# Western_Aero_2020.net
KiCad netlist of a schematic drawn in EAGLE
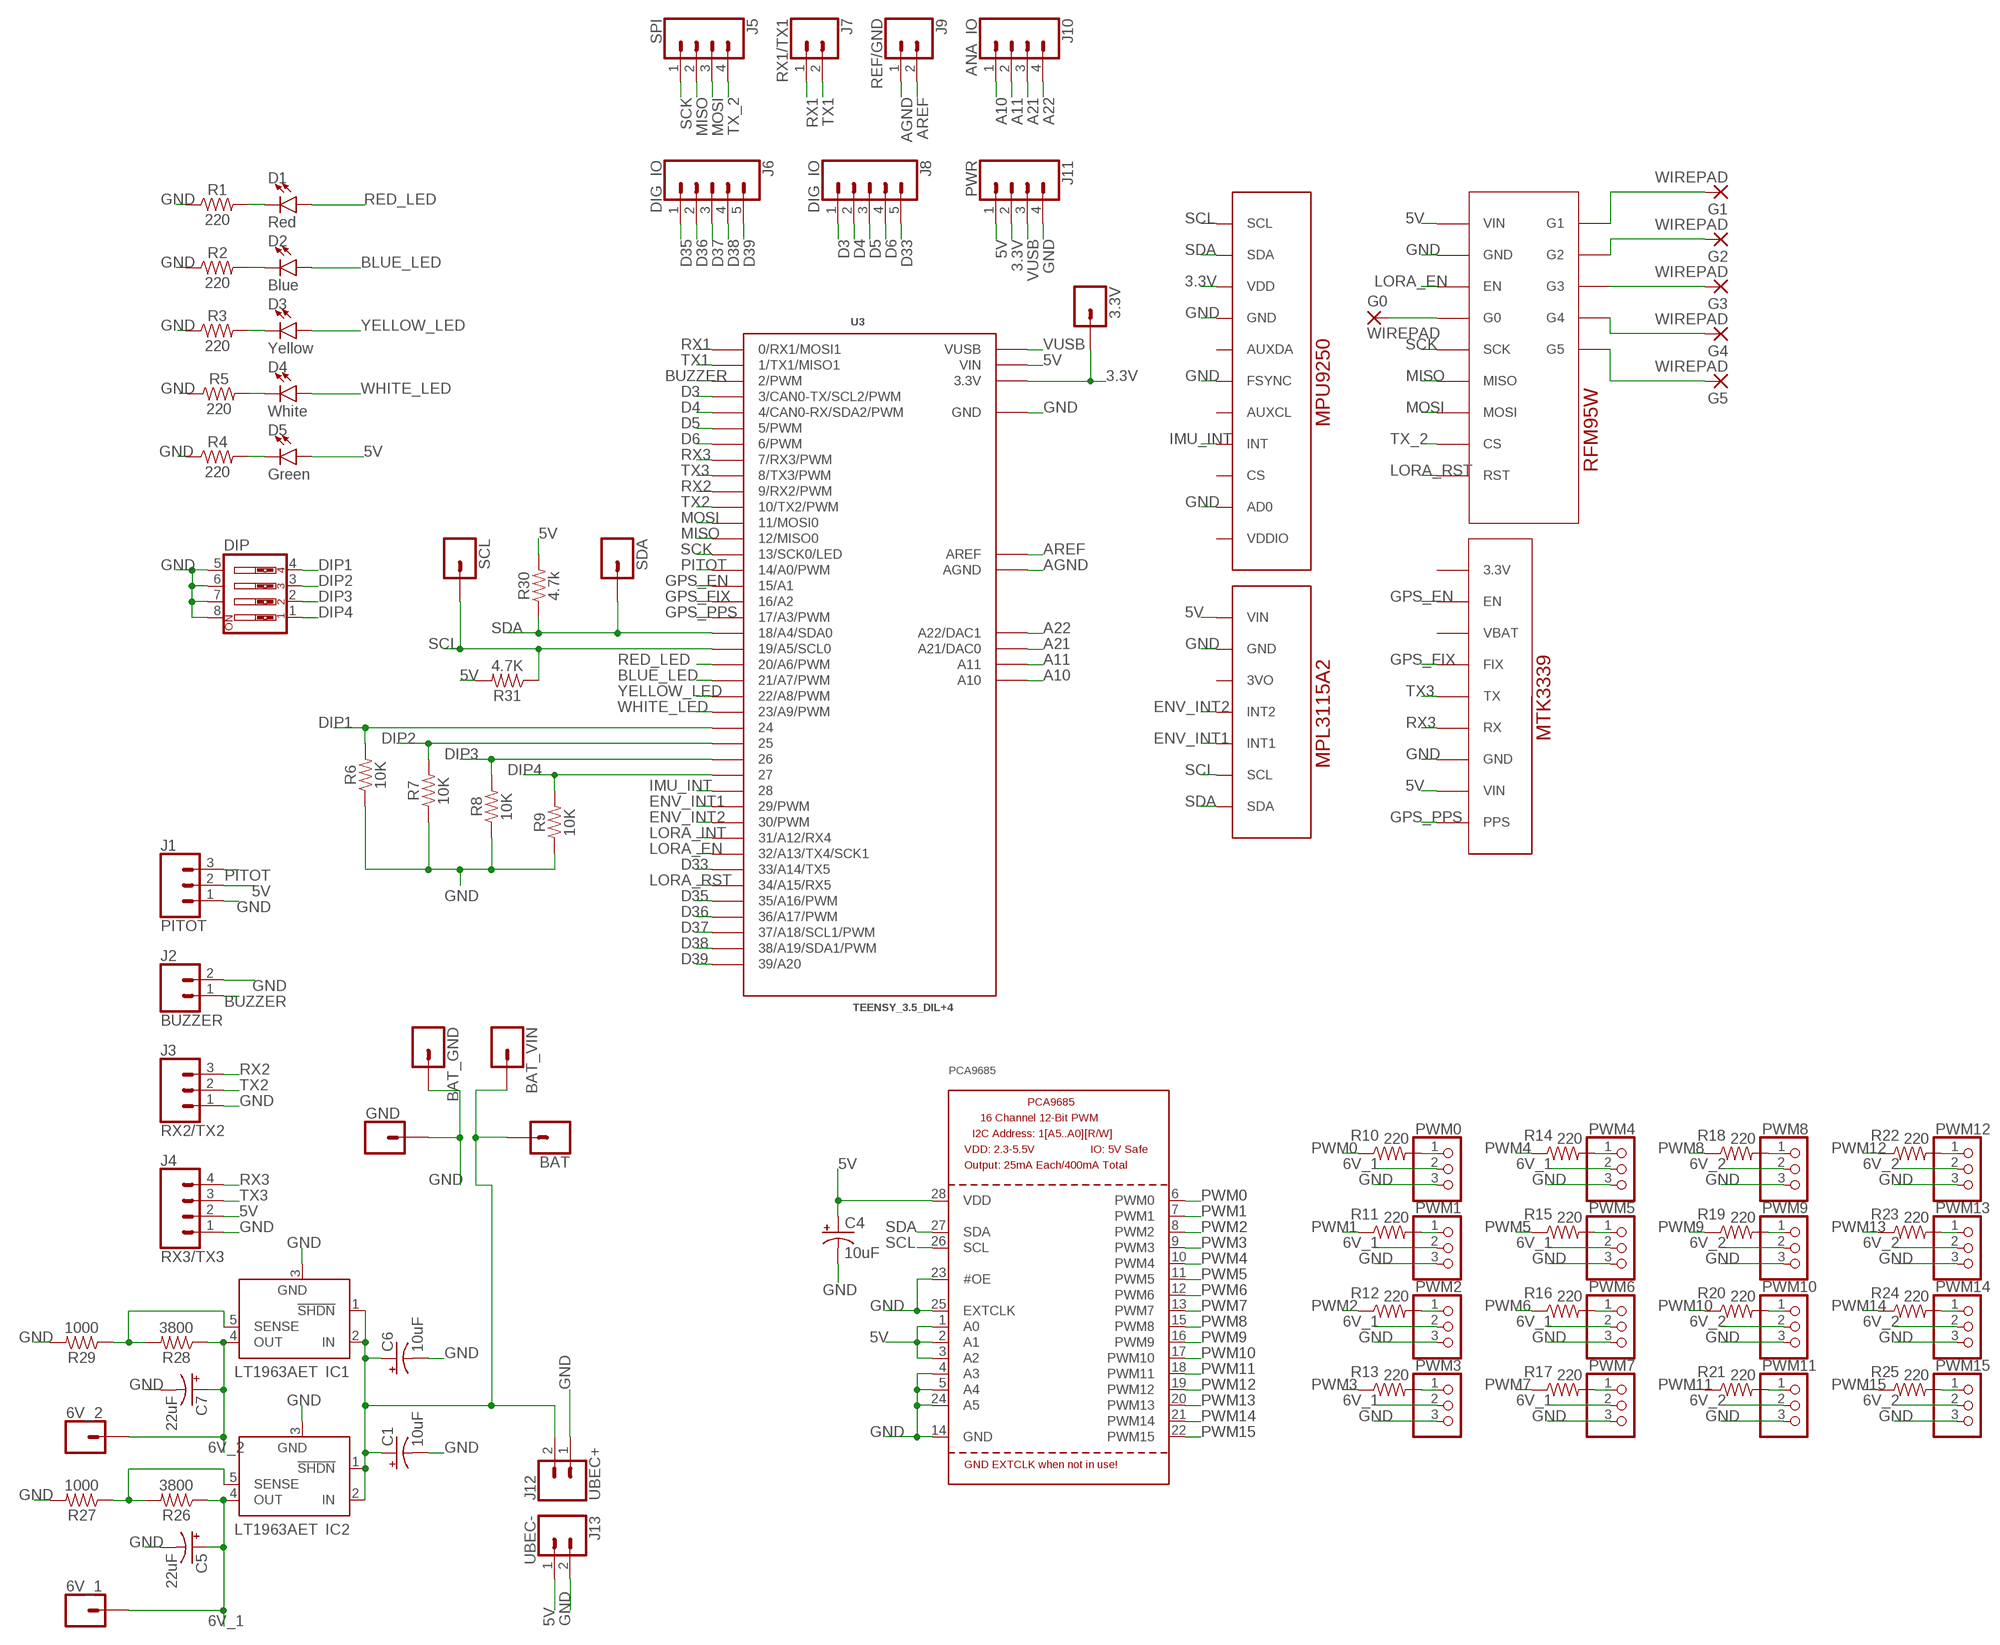
[diagram p0: schematic, sheet 1]

(export (version "E")
  (design (tool "Eeschema 10.0.6"))
  (components
    (comp (ref "3.3V")
      (value "CONN_01")
      (footprint "eagle-import:1X01")
      (libsource (lib "eagle-import") (part "CONN_01"))
    )
    (comp (ref "6V_1")
      (value "CONN_01")
      (footprint "eagle-import:1X01")
      (libsource (lib "eagle-import") (part "CONN_01"))
    )
    (comp (ref "6V_2")
      (value "CONN_01")
      (footprint "eagle-import:1X01")
      (libsource (lib "eagle-import") (part "CONN_01"))
    )
    (comp (ref "BAT")
      (value "CONN_01")
      (footprint "eagle-import:1X01")
      (libsource (lib "eagle-import") (part "CONN_01"))
    )
    (comp (ref "BAT_GND")
      (value "CONN_01")
      (footprint "eagle-import:1X01")
      (libsource (lib "eagle-import") (part "CONN_01"))
    )
    (comp (ref "BAT_VIN")
      (value "CONN_01")
      (footprint "eagle-import:1X01")
      (libsource (lib "eagle-import") (part "CONN_01"))
    )
    (comp (ref "C1")
      (value "10uF")
      (footprint "eagle-import:CPOL-RADIAL-2.5MM-5MM")
      (libsource (lib "eagle-import") (part "10UF-POLAR-RADIAL-2.5MM-25V-20%"))
    )
    (comp (ref "C4")
      (value "10uF")
      (footprint "eagle-import:CPOL-RADIAL-2.5MM-5MM")
      (libsource (lib "eagle-import") (part "10UF-POLAR-RADIAL-2.5MM-25V-20%"))
    )
    (comp (ref "C5")
      (value "22uF")
      (footprint "eagle-import:CPOL-RADIAL-2.5MM-5MM")
      (libsource (lib "eagle-import") (part "10UF-POLAR-RADIAL-2.5MM-25V-20%"))
    )
    (comp (ref "C6")
      (value "10uF")
      (footprint "eagle-import:CPOL-RADIAL-2.5MM-5MM")
      (libsource (lib "eagle-import") (part "10UF-POLAR-RADIAL-2.5MM-25V-20%"))
    )
    (comp (ref "C7")
      (value "22uF")
      (footprint "eagle-import:CPOL-RADIAL-2.5MM-5MM")
      (libsource (lib "eagle-import") (part "10UF-POLAR-RADIAL-2.5MM-25V-20%"))
    )
    (comp (ref "D1")
      (value "Red")
      (footprint "eagle-import:LED_3MM")
      (libsource (lib "eagle-import") (part "LED3MM"))
    )
    (comp (ref "D2")
      (value "Blue")
      (footprint "eagle-import:LED_3MM")
      (libsource (lib "eagle-import") (part "LED3MM"))
    )
    (comp (ref "D3")
      (value "Yellow")
      (footprint "eagle-import:LED_3MM")
      (libsource (lib "eagle-import") (part "LED3MM"))
    )
    (comp (ref "D4")
      (value "White")
      (footprint "eagle-import:LED_3MM")
      (libsource (lib "eagle-import") (part "LED3MM"))
    )
    (comp (ref "D5")
      (value "Green")
      (footprint "eagle-import:LED_3MM")
      (libsource (lib "eagle-import") (part "LED3MM"))
    )
    (comp (ref "DIP")
      (value "SW_DIP-4")
      (footprint "eagle-import:EDG-04")
      (libsource (lib "eagle-import") (part "SW_DIP-4"))
    )
    (comp (ref "G0")
      (value "WIREPAD")
      (footprint "eagle-import:2,15_1,0")
      (libsource (lib "eagle-import") (part "WIREPAD2,15/1,0"))
    )
    (comp (ref "G1")
      (value "WIREPAD")
      (footprint "eagle-import:2,15_1,0")
      (libsource (lib "eagle-import") (part "WIREPAD2,15/1,0"))
    )
    (comp (ref "G2")
      (value "WIREPAD")
      (footprint "eagle-import:2,15_1,0")
      (libsource (lib "eagle-import") (part "WIREPAD2,15/1,0"))
    )
    (comp (ref "G3")
      (value "WIREPAD")
      (footprint "eagle-import:2,15_1,0")
      (libsource (lib "eagle-import") (part "WIREPAD2,15/1,0"))
    )
    (comp (ref "G4")
      (value "WIREPAD")
      (footprint "eagle-import:2,15_1,0")
      (libsource (lib "eagle-import") (part "WIREPAD2,15/1,0"))
    )
    (comp (ref "G5")
      (value "WIREPAD")
      (footprint "eagle-import:2,15_1,0")
      (libsource (lib "eagle-import") (part "WIREPAD2,15/1,0"))
    )
    (comp (ref "GND")
      (value "CONN_01")
      (footprint "eagle-import:1X01")
      (libsource (lib "eagle-import") (part "CONN_01"))
    )
    (comp (ref "IC1")
      (value "LT1963AET")
      (footprint "eagle-import:TO220-5")
      (libsource (lib "eagle-import") (part "LT1963AET"))
    )
    (comp (ref "IC2")
      (value "LT1963AET")
      (footprint "eagle-import:TO220-5")
      (libsource (lib "eagle-import") (part "LT1963AET"))
    )
    (comp (ref "J1")
      (value "PITOT")
      (footprint "eagle-import:1X03")
      (libsource (lib "eagle-import") (part "CONN_03"))
    )
    (comp (ref "J2")
      (value "BUZZER")
      (footprint "eagle-import:1X02")
      (libsource (lib "eagle-import") (part "CONN_02"))
    )
    (comp (ref "J3")
      (value "RX2/TX2")
      (footprint "eagle-import:1X03")
      (libsource (lib "eagle-import") (part "CONN_03"))
    )
    (comp (ref "J4")
      (value "RX3/TX3")
      (footprint "eagle-import:1X04")
      (libsource (lib "eagle-import") (part "CONN_04"))
    )
    (comp (ref "J5")
      (value "SPI")
      (footprint "eagle-import:1X04")
      (libsource (lib "eagle-import") (part "CONN_04"))
    )
    (comp (ref "J6")
      (value "DIG_IO")
      (footprint "eagle-import:1X05")
      (libsource (lib "eagle-import") (part "CONN_05"))
    )
    (comp (ref "J7")
      (value "RX1/TX1")
      (footprint "eagle-import:1X02")
      (libsource (lib "eagle-import") (part "CONN_02"))
    )
    (comp (ref "J8")
      (value "DIG_IO")
      (footprint "eagle-import:1X05")
      (libsource (lib "eagle-import") (part "CONN_05"))
    )
    (comp (ref "J9")
      (value "REF/GND")
      (footprint "eagle-import:1X02")
      (libsource (lib "eagle-import") (part "CONN_02"))
    )
    (comp (ref "J10")
      (value "ANA_IO")
      (footprint "eagle-import:1X04")
      (libsource (lib "eagle-import") (part "CONN_04"))
    )
    (comp (ref "J11")
      (value "PWR")
      (footprint "eagle-import:1X04")
      (libsource (lib "eagle-import") (part "CONN_04"))
    )
    (comp (ref "J12")
      (value "UBEC+")
      (footprint "eagle-import:1X02")
      (libsource (lib "eagle-import") (part "CONN_02"))
    )
    (comp (ref "J13")
      (value "UBEC-")
      (footprint "eagle-import:1X02")
      (libsource (lib "eagle-import") (part "CONN_02"))
    )
    (comp (ref "JP1")
      (value "PWM0")
      (footprint "eagle-import:1X03")
      (libsource (lib "eagle-import") (part "PINHD-1X3"))
    )
    (comp (ref "JP2")
      (value "PWM1")
      (footprint "eagle-import:1X03")
      (libsource (lib "eagle-import") (part "PINHD-1X3"))
    )
    (comp (ref "JP3")
      (value "PWM2")
      (footprint "eagle-import:1X03")
      (libsource (lib "eagle-import") (part "PINHD-1X3"))
    )
    (comp (ref "JP4")
      (value "PWM3")
      (footprint "eagle-import:1X03")
      (libsource (lib "eagle-import") (part "PINHD-1X3"))
    )
    (comp (ref "JP5")
      (value "PWM4")
      (footprint "eagle-import:1X03")
      (libsource (lib "eagle-import") (part "PINHD-1X3"))
    )
    (comp (ref "JP6")
      (value "PWM5")
      (footprint "eagle-import:1X03")
      (libsource (lib "eagle-import") (part "PINHD-1X3"))
    )
    (comp (ref "JP7")
      (value "PWM6")
      (footprint "eagle-import:1X03")
      (libsource (lib "eagle-import") (part "PINHD-1X3"))
    )
    (comp (ref "JP8")
      (value "PWM7")
      (footprint "eagle-import:1X03")
      (libsource (lib "eagle-import") (part "PINHD-1X3"))
    )
    (comp (ref "JP9")
      (value "PWM8")
      (footprint "eagle-import:1X03")
      (libsource (lib "eagle-import") (part "PINHD-1X3"))
    )
    (comp (ref "JP10")
      (value "PWM9")
      (footprint "eagle-import:1X03")
      (libsource (lib "eagle-import") (part "PINHD-1X3"))
    )
    (comp (ref "JP11")
      (value "PWM10")
      (footprint "eagle-import:1X03")
      (libsource (lib "eagle-import") (part "PINHD-1X3"))
    )
    (comp (ref "JP12")
      (value "PWM11")
      (footprint "eagle-import:1X03")
      (libsource (lib "eagle-import") (part "PINHD-1X3"))
    )
    (comp (ref "JP13")
      (value "PWM12")
      (footprint "eagle-import:1X03")
      (libsource (lib "eagle-import") (part "PINHD-1X3"))
    )
    (comp (ref "JP14")
      (value "PWM13")
      (footprint "eagle-import:1X03")
      (libsource (lib "eagle-import") (part "PINHD-1X3"))
    )
    (comp (ref "JP15")
      (value "PWM14")
      (footprint "eagle-import:1X03")
      (libsource (lib "eagle-import") (part "PINHD-1X3"))
    )
    (comp (ref "JP16")
      (value "PWM15")
      (footprint "eagle-import:1X03")
      (libsource (lib "eagle-import") (part "PINHD-1X3"))
    )
    (comp (ref "PCA9685")
      (value "PCA9685")
      (footprint "eagle-import:TSSOP28")
      (libsource (lib "eagle-import") (part "PCA9685"))
    )
    (comp (ref "R1")
      (value "220")
      (footprint "eagle-import:AXIAL-0.3")
      (libsource (lib "eagle-import") (part "330OHM-HORIZ-1/10W-5%"))
    )
    (comp (ref "R2")
      (value "220")
      (footprint "eagle-import:AXIAL-0.3")
      (libsource (lib "eagle-import") (part "330OHM-HORIZ-1/10W-5%"))
    )
    (comp (ref "R3")
      (value "220")
      (footprint "eagle-import:AXIAL-0.3")
      (libsource (lib "eagle-import") (part "330OHM-HORIZ-1/10W-5%"))
    )
    (comp (ref "R4")
      (value "220")
      (footprint "eagle-import:AXIAL-0.3")
      (libsource (lib "eagle-import") (part "330OHM-HORIZ-1/10W-5%"))
    )
    (comp (ref "R5")
      (value "220")
      (footprint "eagle-import:AXIAL-0.3")
      (libsource (lib "eagle-import") (part "330OHM-HORIZ-1/10W-5%"))
    )
    (comp (ref "R6")
      (value "10K")
      (footprint "eagle-import:AXIAL-0.3")
      (libsource (lib "eagle-import") (part "330OHM-HORIZ-1/10W-5%"))
    )
    (comp (ref "R7")
      (value "10K")
      (footprint "eagle-import:AXIAL-0.3")
      (libsource (lib "eagle-import") (part "330OHM-HORIZ-1/10W-5%"))
    )
    (comp (ref "R8")
      (value "10K")
      (footprint "eagle-import:AXIAL-0.3")
      (libsource (lib "eagle-import") (part "330OHM-HORIZ-1/10W-5%"))
    )
    (comp (ref "R9")
      (value "10K")
      (footprint "eagle-import:AXIAL-0.3")
      (libsource (lib "eagle-import") (part "330OHM-HORIZ-1/10W-5%"))
    )
    (comp (ref "R10")
      (value "220")
      (footprint "eagle-import:AXIAL-0.3")
      (libsource (lib "eagle-import") (part "330OHM-HORIZ-1/10W-5%"))
    )
    (comp (ref "R11")
      (value "220")
      (footprint "eagle-import:AXIAL-0.3")
      (libsource (lib "eagle-import") (part "330OHM-HORIZ-1/10W-5%"))
    )
    (comp (ref "R12")
      (value "220")
      (footprint "eagle-import:AXIAL-0.3")
      (libsource (lib "eagle-import") (part "330OHM-HORIZ-1/10W-5%"))
    )
    (comp (ref "R13")
      (value "220")
      (footprint "eagle-import:AXIAL-0.3")
      (libsource (lib "eagle-import") (part "330OHM-HORIZ-1/10W-5%"))
    )
    (comp (ref "R14")
      (value "220")
      (footprint "eagle-import:AXIAL-0.3")
      (libsource (lib "eagle-import") (part "330OHM-HORIZ-1/10W-5%"))
    )
    (comp (ref "R15")
      (value "220")
      (footprint "eagle-import:AXIAL-0.3")
      (libsource (lib "eagle-import") (part "330OHM-HORIZ-1/10W-5%"))
    )
    (comp (ref "R16")
      (value "220")
      (footprint "eagle-import:AXIAL-0.3")
      (libsource (lib "eagle-import") (part "330OHM-HORIZ-1/10W-5%"))
    )
    (comp (ref "R17")
      (value "220")
      (footprint "eagle-import:AXIAL-0.3")
      (libsource (lib "eagle-import") (part "330OHM-HORIZ-1/10W-5%"))
    )
    (comp (ref "R18")
      (value "220")
      (footprint "eagle-import:AXIAL-0.3")
      (libsource (lib "eagle-import") (part "330OHM-HORIZ-1/10W-5%"))
    )
    (comp (ref "R19")
      (value "220")
      (footprint "eagle-import:AXIAL-0.3")
      (libsource (lib "eagle-import") (part "330OHM-HORIZ-1/10W-5%"))
    )
    (comp (ref "R20")
      (value "220")
      (footprint "eagle-import:AXIAL-0.3")
      (libsource (lib "eagle-import") (part "330OHM-HORIZ-1/10W-5%"))
    )
    (comp (ref "R21")
      (value "220")
      (footprint "eagle-import:AXIAL-0.3")
      (libsource (lib "eagle-import") (part "330OHM-HORIZ-1/10W-5%"))
    )
    (comp (ref "R22")
      (value "220")
      (footprint "eagle-import:AXIAL-0.3")
      (libsource (lib "eagle-import") (part "330OHM-HORIZ-1/10W-5%"))
    )
    (comp (ref "R23")
      (value "220")
      (footprint "eagle-import:AXIAL-0.3")
      (libsource (lib "eagle-import") (part "330OHM-HORIZ-1/10W-5%"))
    )
    (comp (ref "R24")
      (value "220")
      (footprint "eagle-import:AXIAL-0.3")
      (libsource (lib "eagle-import") (part "330OHM-HORIZ-1/10W-5%"))
    )
    (comp (ref "R25")
      (value "220")
      (footprint "eagle-import:AXIAL-0.3")
      (libsource (lib "eagle-import") (part "330OHM-HORIZ-1/10W-5%"))
    )
    (comp (ref "R26")
      (value "3800")
      (footprint "eagle-import:AXIAL-0.3")
      (libsource (lib "eagle-import") (part "330OHM-HORIZ-1/10W-5%"))
    )
    (comp (ref "R27")
      (value "1000")
      (footprint "eagle-import:AXIAL-0.3")
      (libsource (lib "eagle-import") (part "330OHM-HORIZ-1/10W-5%"))
    )
    (comp (ref "R28")
      (value "3800")
      (footprint "eagle-import:AXIAL-0.3")
      (libsource (lib "eagle-import") (part "330OHM-HORIZ-1/10W-5%"))
    )
    (comp (ref "R29")
      (value "1000")
      (footprint "eagle-import:AXIAL-0.3")
      (libsource (lib "eagle-import") (part "330OHM-HORIZ-1/10W-5%"))
    )
    (comp (ref "R30")
      (value "4.7k")
      (footprint "eagle-import:AXIAL-0.3")
      (libsource (lib "eagle-import") (part "330OHM-HORIZ-1/10W-5%"))
    )
    (comp (ref "R31")
      (value "4.7K")
      (footprint "eagle-import:AXIAL-0.3")
      (libsource (lib "eagle-import") (part "330OHM-HORIZ-1/10W-5%"))
    )
    (comp (ref "SCL")
      (value "CONN_01")
      (footprint "eagle-import:1X01")
      (libsource (lib "eagle-import") (part "CONN_01"))
    )
    (comp (ref "SDA")
      (value "CONN_01")
      (footprint "eagle-import:1X01")
      (libsource (lib "eagle-import") (part "CONN_01"))
    )
    (comp (ref "U3")
      (value "TEENSY_3.5_DIL+4")
      (footprint "eagle-import:TEENSY_3.5_DIL+4")
      (libsource (lib "eagle-import") (part "TEENSY_3.5_DIL+4"))
    )
    (comp (ref "U5")
      (value "SPARKFUN_MPU9250_IMU")
      (footprint "eagle-import:SPARKFUN_MPU9250_IMU")
      (libsource (lib "eagle-import") (part "SPARKFUN_MPU9250_IMU"))
    )
    (comp (ref "U6")
      (value "ADAFRUIT_MPL3115A2_BAROMETER")
      (footprint "eagle-import:ADAFRUIT_MPL3115A2_BAROMETER")
      (libsource (lib "eagle-import") (part "ADAFRUIT_MPL3115A2_BAROMETER"))
    )
    (comp (ref "U8")
      (value "ADAFRUIT_RFM95W_LORA_RADIO")
      (footprint "eagle-import:ADAFRUIT_RFM95W_LORA_RADIO")
      (libsource (lib "eagle-import") (part "ADAFRUIT_RFM95W_LORA_RADIO"))
    )
    (comp (ref "U9")
      (value "ADAFRUIT_MTK3339_GPS")
      (footprint "eagle-import:ADAFRUIT_MTK3339_GPS")
      (libsource (lib "eagle-import") (part "ADAFRUIT_MTK3339_GPS"))
    )
  )
  (nets
    (net (code "1") (name "/3.3V") (class "Default")
      (node (ref "3.3V") (pin "1") (pinfunction "1_1") (pintype "passive"))
      (node (ref "J11") (pin "2") (pinfunction "2_2") (pintype "passive"))
      (node (ref "U3") (pin "3.3V") (pinfunction "3.3V_3.3V") (pintype "power_in"))
      (node (ref "U3") (pin "3.3V3") (pinfunction "3.3V_3.3V3") (pintype "power_in"))
      (node (ref "U5") (pin "VDD") (pinfunction "VDD_VDD") (pintype "bidirectional"))
    )
    (net (code "2") (name "/5V") (class "Default")
      (node (ref "C4") (pin "1") (pinfunction "+_1") (pintype "passive"))
      (node (ref "D5") (pin "A") (pinfunction "A_A") (pintype "passive"))
      (node (ref "J1") (pin "2") (pinfunction "2_2") (pintype "passive"))
      (node (ref "J11") (pin "1") (pinfunction "1_1") (pintype "passive"))
      (node (ref "J13") (pin "1") (pinfunction "1_1") (pintype "passive"))
      (node (ref "J4") (pin "2") (pinfunction "2_2") (pintype "passive"))
      (node (ref "PCA9685") (pin "1") (pinfunction "A0_1") (pintype "bidirectional"))
      (node (ref "PCA9685") (pin "2") (pinfunction "A1_2") (pintype "bidirectional"))
      (node (ref "PCA9685") (pin "28") (pinfunction "VDD_28") (pintype "power_in"))
      (node (ref "PCA9685") (pin "3") (pinfunction "A2_3") (pintype "bidirectional"))
      (node (ref "R30") (pin "P$2") (pinfunction "2_P$2") (pintype "passive"))
      (node (ref "R31") (pin "P$2") (pinfunction "2_P$2") (pintype "passive"))
      (node (ref "U3") (pin "VIN") (pinfunction "VIN_VIN") (pintype "power_in"))
      (node (ref "U6") (pin "VIN") (pinfunction "VIN_VIN") (pintype "bidirectional"))
      (node (ref "U8") (pin "1") (pinfunction "VIN_1") (pintype "bidirectional"))
      (node (ref "U9") (pin "VIN") (pinfunction "VIN_VIN") (pintype "bidirectional"))
    )
    (net (code "3") (name "/6V_1") (class "Default")
      (node (ref "6V_1") (pin "1") (pinfunction "1_1") (pintype "passive"))
      (node (ref "C5") (pin "1") (pinfunction "+_1") (pintype "passive"))
      (node (ref "IC2") (pin "4") (pinfunction "OUT_4") (pintype "passive"))
      (node (ref "JP1") (pin "2") (pinfunction "2_2") (pintype "passive"))
      (node (ref "JP2") (pin "2") (pinfunction "2_2") (pintype "passive"))
      (node (ref "JP3") (pin "2") (pinfunction "2_2") (pintype "passive"))
      (node (ref "JP4") (pin "2") (pinfunction "2_2") (pintype "passive"))
      (node (ref "JP5") (pin "2") (pinfunction "2_2") (pintype "passive"))
      (node (ref "JP6") (pin "2") (pinfunction "2_2") (pintype "passive"))
      (node (ref "JP7") (pin "2") (pinfunction "2_2") (pintype "passive"))
      (node (ref "JP8") (pin "2") (pinfunction "2_2") (pintype "passive"))
      (node (ref "R26") (pin "P$1") (pinfunction "1_P$1") (pintype "passive"))
    )
    (net (code "4") (name "/6V_2") (class "Default")
      (node (ref "6V_2") (pin "1") (pinfunction "1_1") (pintype "passive"))
      (node (ref "C7") (pin "1") (pinfunction "+_1") (pintype "passive"))
      (node (ref "IC1") (pin "4") (pinfunction "OUT_4") (pintype "passive"))
      (node (ref "JP10") (pin "2") (pinfunction "2_2") (pintype "passive"))
      (node (ref "JP11") (pin "2") (pinfunction "2_2") (pintype "passive"))
      (node (ref "JP12") (pin "2") (pinfunction "2_2") (pintype "passive"))
      (node (ref "JP13") (pin "2") (pinfunction "2_2") (pintype "passive"))
      (node (ref "JP14") (pin "2") (pinfunction "2_2") (pintype "passive"))
      (node (ref "JP15") (pin "2") (pinfunction "2_2") (pintype "passive"))
      (node (ref "JP16") (pin "2") (pinfunction "2_2") (pintype "passive"))
      (node (ref "JP9") (pin "2") (pinfunction "2_2") (pintype "passive"))
      (node (ref "R28") (pin "P$1") (pinfunction "1_P$1") (pintype "passive"))
    )
    (net (code "5") (name "/A10") (class "Default")
      (node (ref "J10") (pin "1") (pinfunction "1_1") (pintype "passive"))
      (node (ref "U3") (pin "A10") (pinfunction "A10_A10") (pintype "bidirectional"))
    )
    (net (code "6") (name "/A11") (class "Default")
      (node (ref "J10") (pin "2") (pinfunction "2_2") (pintype "passive"))
      (node (ref "U3") (pin "A11") (pinfunction "A11_A11") (pintype "bidirectional"))
    )
    (net (code "7") (name "/A21") (class "Default")
      (node (ref "J10") (pin "3") (pinfunction "3_3") (pintype "passive"))
      (node (ref "U3") (pin "A21") (pinfunction "A21/DAC0_A21") (pintype "bidirectional"))
    )
    (net (code "8") (name "/A22") (class "Default")
      (node (ref "J10") (pin "4") (pinfunction "4_4") (pintype "passive"))
      (node (ref "U3") (pin "A22") (pinfunction "A22/DAC1_A22") (pintype "bidirectional"))
    )
    (net (code "9") (name "/AGND") (class "Default")
      (node (ref "J9") (pin "1") (pinfunction "1_1") (pintype "passive"))
      (node (ref "U3") (pin "AGND") (pinfunction "AGND_AGND") (pintype "power_in"))
    )
    (net (code "10") (name "/AREF") (class "Default")
      (node (ref "J9") (pin "2") (pinfunction "2_2") (pintype "passive"))
      (node (ref "U3") (pin "AREF") (pinfunction "AREF_AREF") (pintype "power_in"))
    )
    (net (code "11") (name "/BLUE_LED") (class "Default")
      (node (ref "D2") (pin "A") (pinfunction "A_A") (pintype "passive"))
      (node (ref "U3") (pin "21/A7") (pinfunction "21/A7/PWM_21/A7") (pintype "bidirectional"))
    )
    (net (code "12") (name "/BUZZER") (class "Default")
      (node (ref "J2") (pin "1") (pinfunction "1_1") (pintype "passive"))
      (node (ref "U3") (pin "2") (pinfunction "2/PWM_2") (pintype "bidirectional"))
    )
    (net (code "13") (name "/D3") (class "Default")
      (node (ref "J8") (pin "1") (pinfunction "1_1") (pintype "passive"))
      (node (ref "U3") (pin "3") (pinfunction "3/CAN0-TX/SCL2/PWM_3") (pintype "bidirectional"))
    )
    (net (code "14") (name "/D4") (class "Default")
      (node (ref "J8") (pin "2") (pinfunction "2_2") (pintype "passive"))
      (node (ref "U3") (pin "4") (pinfunction "4/CAN0-RX/SDA2/PWM_4") (pintype "bidirectional"))
    )
    (net (code "15") (name "/D5") (class "Default")
      (node (ref "J8") (pin "3") (pinfunction "3_3") (pintype "passive"))
      (node (ref "U3") (pin "5") (pinfunction "5/PWM_5") (pintype "bidirectional"))
    )
    (net (code "16") (name "/D6") (class "Default")
      (node (ref "J8") (pin "4") (pinfunction "4_4") (pintype "passive"))
      (node (ref "U3") (pin "6") (pinfunction "6/PWM_6") (pintype "bidirectional"))
    )
    (net (code "17") (name "/D33") (class "Default")
      (node (ref "J8") (pin "5") (pinfunction "5_5") (pintype "passive"))
      (node (ref "U3") (pin "33/A14") (pinfunction "33/A14/TX5_33/A14") (pintype "bidirectional"))
    )
    (net (code "18") (name "/D35") (class "Default")
      (node (ref "J6") (pin "1") (pinfunction "1_1") (pintype "passive"))
      (node (ref "U3") (pin "35/A16") (pinfunction "35/A16/PWM_35/A16") (pintype "bidirectional"))
    )
    (net (code "19") (name "/D36") (class "Default")
      (node (ref "J6") (pin "2") (pinfunction "2_2") (pintype "passive"))
      (node (ref "U3") (pin "36/A17") (pinfunction "36/A17/PWM_36/A17") (pintype "bidirectional"))
    )
    (net (code "20") (name "/D37") (class "Default")
      (node (ref "J6") (pin "3") (pinfunction "3_3") (pintype "passive"))
      (node (ref "U3") (pin "37/A18") (pinfunction "37/A18/SCL1/PWM_37/A18") (pintype "bidirectional"))
    )
    (net (code "21") (name "/D38") (class "Default")
      (node (ref "J6") (pin "4") (pinfunction "4_4") (pintype "passive"))
      (node (ref "U3") (pin "38/A19") (pinfunction "38/A19/SDA1/PWM_38/A19") (pintype "bidirectional"))
    )
    (net (code "22") (name "/D39") (class "Default")
      (node (ref "J6") (pin "5") (pinfunction "5_5") (pintype "passive"))
      (node (ref "U3") (pin "39/A20") (pinfunction "39/A20_39/A20") (pintype "bidirectional"))
    )
    (net (code "23") (name "/DIP1") (class "Default")
      (node (ref "DIP") (pin "4") (pinfunction "4_4") (pintype "passive"))
      (node (ref "R6") (pin "P$2") (pinfunction "2_P$2") (pintype "passive"))
      (node (ref "U3") (pin "24") (pinfunction "24_24") (pintype "bidirectional"))
    )
    (net (code "24") (name "/DIP2") (class "Default")
      (node (ref "DIP") (pin "3") (pinfunction "3_3") (pintype "passive"))
      (node (ref "R7") (pin "P$2") (pinfunction "2_P$2") (pintype "passive"))
      (node (ref "U3") (pin "25") (pinfunction "25_25") (pintype "bidirectional"))
    )
    (net (code "25") (name "/DIP3") (class "Default")
      (node (ref "DIP") (pin "2") (pinfunction "2_2") (pintype "passive"))
      (node (ref "R8") (pin "P$2") (pinfunction "2_P$2") (pintype "passive"))
      (node (ref "U3") (pin "26") (pinfunction "26_26") (pintype "bidirectional"))
    )
    (net (code "26") (name "/DIP4") (class "Default")
      (node (ref "DIP") (pin "1") (pinfunction "1_1") (pintype "passive"))
      (node (ref "R9") (pin "P$2") (pinfunction "2_P$2") (pintype "passive"))
      (node (ref "U3") (pin "27") (pinfunction "27_27") (pintype "bidirectional"))
    )
    (net (code "27") (name "/ENV_INT1") (class "Default")
      (node (ref "U3") (pin "29") (pinfunction "29/PWM_29") (pintype "bidirectional"))
      (node (ref "U6") (pin "INT1") (pinfunction "INT1_INT1") (pintype "bidirectional"))
    )
    (net (code "28") (name "/ENV_INT2") (class "Default")
      (node (ref "U3") (pin "30") (pinfunction "30/PWM_30") (pintype "bidirectional"))
      (node (ref "U6") (pin "INT2") (pinfunction "INT2_INT2") (pintype "bidirectional"))
    )
    (net (code "29") (name "/GND") (class "Default")
      (node (ref "BAT_GND") (pin "1") (pinfunction "1_1") (pintype "passive"))
      (node (ref "C1") (pin "2") (pinfunction "-_2") (pintype "passive"))
      (node (ref "C4") (pin "2") (pinfunction "-_2") (pintype "passive"))
      (node (ref "C5") (pin "2") (pinfunction "-_2") (pintype "passive"))
      (node (ref "C6") (pin "2") (pinfunction "-_2") (pintype "passive"))
      (node (ref "C7") (pin "2") (pinfunction "-_2") (pintype "passive"))
      (node (ref "DIP") (pin "5") (pinfunction "5_5") (pintype "passive"))
      (node (ref "DIP") (pin "6") (pinfunction "6_6") (pintype "passive"))
      (node (ref "DIP") (pin "7") (pinfunction "7_7") (pintype "passive"))
      (node (ref "DIP") (pin "8") (pinfunction "8_8") (pintype "passive"))
      (node (ref "GND") (pin "1") (pinfunction "1_1") (pintype "passive"))
      (node (ref "IC1") (pin "3") (pinfunction "GND_3") (pintype "power_in"))
      (node (ref "IC2") (pin "3") (pinfunction "GND_3") (pintype "power_in"))
      (node (ref "J1") (pin "1") (pinfunction "1_1") (pintype "passive"))
      (node (ref "J11") (pin "4") (pinfunction "4_4") (pintype "passive"))
      (node (ref "J12") (pin "1") (pinfunction "1_1") (pintype "passive"))
      (node (ref "J13") (pin "2") (pinfunction "2_2") (pintype "passive"))
      (node (ref "J2") (pin "2") (pinfunction "2_2") (pintype "passive"))
      (node (ref "J3") (pin "1") (pinfunction "1_1") (pintype "passive"))
      (node (ref "J4") (pin "1") (pinfunction "1_1") (pintype "passive"))
      (node (ref "JP1") (pin "3") (pinfunction "3_3") (pintype "passive"))
      (node (ref "JP10") (pin "3") (pinfunction "3_3") (pintype "passive"))
      (node (ref "JP11") (pin "3") (pinfunction "3_3") (pintype "passive"))
      (node (ref "JP12") (pin "3") (pinfunction "3_3") (pintype "passive"))
      (node (ref "JP13") (pin "3") (pinfunction "3_3") (pintype "passive"))
      (node (ref "JP14") (pin "3") (pinfunction "3_3") (pintype "passive"))
      (node (ref "JP15") (pin "3") (pinfunction "3_3") (pintype "passive"))
      (node (ref "JP16") (pin "3") (pinfunction "3_3") (pintype "passive"))
      (node (ref "JP2") (pin "3") (pinfunction "3_3") (pintype "passive"))
      (node (ref "JP3") (pin "3") (pinfunction "3_3") (pintype "passive"))
      (node (ref "JP4") (pin "3") (pinfunction "3_3") (pintype "passive"))
      (node (ref "JP5") (pin "3") (pinfunction "3_3") (pintype "passive"))
      (node (ref "JP6") (pin "3") (pinfunction "3_3") (pintype "passive"))
      (node (ref "JP7") (pin "3") (pinfunction "3_3") (pintype "passive"))
      (node (ref "JP8") (pin "3") (pinfunction "3_3") (pintype "passive"))
      (node (ref "JP9") (pin "3") (pinfunction "3_3") (pintype "passive"))
      (node (ref "PCA9685") (pin "14") (pinfunction "GND_14") (pintype "power_in"))
      (node (ref "PCA9685") (pin "23") (pinfunction "#OE_23") (pintype "input"))
      (node (ref "PCA9685") (pin "24") (pinfunction "A5_24") (pintype "bidirectional"))
      (node (ref "PCA9685") (pin "25") (pinfunction "EXTCLK_25") (pintype "input"))
      (node (ref "PCA9685") (pin "4") (pinfunction "A3_4") (pintype "bidirectional"))
      (node (ref "PCA9685") (pin "5") (pinfunction "A4_5") (pintype "bidirectional"))
      (node (ref "R1") (pin "P$1") (pinfunction "1_P$1") (pintype "passive"))
      (node (ref "R2") (pin "P$1") (pinfunction "1_P$1") (pintype "passive"))
      (node (ref "R27") (pin "P$2") (pinfunction "2_P$2") (pintype "passive"))
      (node (ref "R29") (pin "P$2") (pinfunction "2_P$2") (pintype "passive"))
      (node (ref "R3") (pin "P$1") (pinfunction "1_P$1") (pintype "passive"))
      (node (ref "R4") (pin "P$1") (pinfunction "1_P$1") (pintype "passive"))
      (node (ref "R5") (pin "P$1") (pinfunction "1_P$1") (pintype "passive"))
      (node (ref "R6") (pin "P$1") (pinfunction "1_P$1") (pintype "passive"))
      (node (ref "R7") (pin "P$1") (pinfunction "1_P$1") (pintype "passive"))
      (node (ref "R8") (pin "P$1") (pinfunction "1_P$1") (pintype "passive"))
      (node (ref "R9") (pin "P$1") (pinfunction "1_P$1") (pintype "passive"))
      (node (ref "U3") (pin "GND") (pinfunction "GND_GND") (pintype "power_in"))
      (node (ref "U3") (pin "GND1") (pinfunction "GND_GND1") (pintype "power_in"))
      (node (ref "U5") (pin "AD0") (pinfunction "AD0_AD0") (pintype "bidirectional"))
      (node (ref "U5") (pin "FSYNC") (pinfunction "FSYNC_FSYNC") (pintype "bidirectional"))
      (node (ref "U5") (pin "GND") (pinfunction "GND_GND") (pintype "bidirectional"))
      (node (ref "U6") (pin "GND") (pinfunction "GND_GND") (pintype "bidirectional"))
      (node (ref "U8") (pin "2") (pinfunction "GND_2") (pintype "bidirectional"))
      (node (ref "U9") (pin "GND") (pinfunction "GND_GND") (pintype "bidirectional"))
    )
    (net (code "30") (name "/GPS_EN") (class "Default")
      (node (ref "U3") (pin "15/A1") (pinfunction "15/A1_15/A1") (pintype "bidirectional"))
      (node (ref "U9") (pin "EN") (pinfunction "EN_EN") (pintype "bidirectional"))
    )
    (net (code "31") (name "/GPS_FIX") (class "Default")
      (node (ref "U3") (pin "16/A2") (pinfunction "16/A2_16/A2") (pintype "bidirectional"))
      (node (ref "U9") (pin "FIX") (pinfunction "FIX_FIX") (pintype "bidirectional"))
    )
    (net (code "32") (name "/GPS_PPS") (class "Default")
      (node (ref "U3") (pin "17/A3") (pinfunction "17/A3/PWM_17/A3") (pintype "bidirectional"))
      (node (ref "U9") (pin "PPS") (pinfunction "PPS_PPS") (pintype "bidirectional"))
    )
    (net (code "33") (name "/IMU_INT") (class "Default")
      (node (ref "U3") (pin "28") (pinfunction "28_28") (pintype "bidirectional"))
      (node (ref "U5") (pin "INT") (pinfunction "INT_INT") (pintype "bidirectional"))
    )
    (net (code "34") (name "/LORA_EN") (class "Default")
      (node (ref "U3") (pin "32/A13") (pinfunction "32/A13/TX4/SCK1_32/A13") (pintype "bidirectional"))
      (node (ref "U8") (pin "3") (pinfunction "EN_3") (pintype "bidirectional"))
    )
    (net (code "35") (name "/LORA_INT") (class "Default")
      (node (ref "U3") (pin "31/A12") (pinfunction "31/A12/RX4_31/A12") (pintype "bidirectional"))
    )
    (net (code "36") (name "/LORA_RST") (class "Default")
      (node (ref "U3") (pin "34/A15") (pinfunction "34/A15/RX5_34/A15") (pintype "bidirectional"))
      (node (ref "U8") (pin "9") (pinfunction "RST_9") (pintype "bidirectional"))
    )
    (net (code "37") (name "/MISO") (class "Default")
      (node (ref "J5") (pin "2") (pinfunction "2_2") (pintype "passive"))
      (node (ref "U3") (pin "12") (pinfunction "12/MISO0_12") (pintype "bidirectional"))
      (node (ref "U8") (pin "6") (pinfunction "MISO_6") (pintype "bidirectional"))
    )
    (net (code "38") (name "/MOSI") (class "Default")
      (node (ref "J5") (pin "3") (pinfunction "3_3") (pintype "passive"))
      (node (ref "U3") (pin "11") (pinfunction "11/MOSI0_11") (pintype "bidirectional"))
      (node (ref "U8") (pin "7") (pinfunction "MOSI_7") (pintype "bidirectional"))
    )
    (net (code "39") (name "/PITOT") (class "Default")
      (node (ref "J1") (pin "3") (pinfunction "3_3") (pintype "passive"))
      (node (ref "U3") (pin "14/A0") (pinfunction "14/A0/PWM_14/A0") (pintype "bidirectional"))
    )
    (net (code "40") (name "/PWM0") (class "Default")
      (node (ref "PCA9685") (pin "6") (pinfunction "PWM0_6") (pintype "output"))
      (node (ref "R10") (pin "P$1") (pinfunction "1_P$1") (pintype "passive"))
    )
    (net (code "41") (name "/PWM1") (class "Default")
      (node (ref "PCA9685") (pin "7") (pinfunction "PWM1_7") (pintype "output"))
      (node (ref "R11") (pin "P$1") (pinfunction "1_P$1") (pintype "passive"))
    )
    (net (code "42") (name "/PWM2") (class "Default")
      (node (ref "PCA9685") (pin "8") (pinfunction "PWM2_8") (pintype "output"))
      (node (ref "R12") (pin "P$1") (pinfunction "1_P$1") (pintype "passive"))
    )
    (net (code "43") (name "/PWM3") (class "Default")
      (node (ref "PCA9685") (pin "9") (pinfunction "PWM3_9") (pintype "output"))
      (node (ref "R13") (pin "P$1") (pinfunction "1_P$1") (pintype "passive"))
    )
    (net (code "44") (name "/PWM4") (class "Default")
      (node (ref "PCA9685") (pin "10") (pinfunction "PWM4_10") (pintype "output"))
      (node (ref "R14") (pin "P$1") (pinfunction "1_P$1") (pintype "passive"))
    )
    (net (code "45") (name "/PWM5") (class "Default")
      (node (ref "PCA9685") (pin "11") (pinfunction "PWM5_11") (pintype "output"))
      (node (ref "R15") (pin "P$1") (pinfunction "1_P$1") (pintype "passive"))
    )
    (net (code "46") (name "/PWM6") (class "Default")
      (node (ref "PCA9685") (pin "12") (pinfunction "PWM6_12") (pintype "output"))
      (node (ref "R16") (pin "P$1") (pinfunction "1_P$1") (pintype "passive"))
    )
    (net (code "47") (name "/PWM7") (class "Default")
      (node (ref "PCA9685") (pin "13") (pinfunction "PWM7_13") (pintype "output"))
      (node (ref "R17") (pin "P$1") (pinfunction "1_P$1") (pintype "passive"))
    )
    (net (code "48") (name "/PWM8") (class "Default")
      (node (ref "PCA9685") (pin "15") (pinfunction "PWM8_15") (pintype "output"))
      (node (ref "R18") (pin "P$1") (pinfunction "1_P$1") (pintype "passive"))
    )
    (net (code "49") (name "/PWM9") (class "Default")
      (node (ref "PCA9685") (pin "16") (pinfunction "PWM9_16") (pintype "output"))
      (node (ref "R19") (pin "P$1") (pinfunction "1_P$1") (pintype "passive"))
    )
    (net (code "50") (name "/PWM10") (class "Default")
      (node (ref "PCA9685") (pin "17") (pinfunction "PWM10_17") (pintype "output"))
      (node (ref "R20") (pin "P$1") (pinfunction "1_P$1") (pintype "passive"))
    )
    (net (code "51") (name "/PWM11") (class "Default")
      (node (ref "PCA9685") (pin "18") (pinfunction "PWM11_18") (pintype "output"))
      (node (ref "R21") (pin "P$1") (pinfunction "1_P$1") (pintype "passive"))
    )
    (net (code "52") (name "/PWM12") (class "Default")
      (node (ref "PCA9685") (pin "19") (pinfunction "PWM12_19") (pintype "output"))
      (node (ref "R22") (pin "P$1") (pinfunction "1_P$1") (pintype "passive"))
    )
    (net (code "53") (name "/PWM13") (class "Default")
      (node (ref "PCA9685") (pin "20") (pinfunction "PWM13_20") (pintype "output"))
      (node (ref "R23") (pin "P$1") (pinfunction "1_P$1") (pintype "passive"))
    )
    (net (code "54") (name "/PWM14") (class "Default")
      (node (ref "PCA9685") (pin "21") (pinfunction "PWM14_21") (pintype "output"))
      (node (ref "R24") (pin "P$1") (pinfunction "1_P$1") (pintype "passive"))
    )
    (net (code "55") (name "/PWM15") (class "Default")
      (node (ref "PCA9685") (pin "22") (pinfunction "PWM15_22") (pintype "output"))
      (node (ref "R25") (pin "P$1") (pinfunction "1_P$1") (pintype "passive"))
    )
    (net (code "56") (name "/RED_LED") (class "Default")
      (node (ref "D1") (pin "A") (pinfunction "A_A") (pintype "passive"))
      (node (ref "U3") (pin "20/A6") (pinfunction "20/A6/PWM_20/A6") (pintype "bidirectional"))
    )
    (net (code "57") (name "/RX1") (class "Default")
      (node (ref "J7") (pin "1") (pinfunction "1_1") (pintype "passive"))
      (node (ref "U3") (pin "0") (pinfunction "0/RX1/MOSI1_0") (pintype "bidirectional"))
    )
    (net (code "58") (name "/RX2") (class "Default")
      (node (ref "J3") (pin "3") (pinfunction "3_3") (pintype "passive"))
      (node (ref "U3") (pin "9") (pinfunction "9/RX2/PWM_9") (pintype "bidirectional"))
    )
    (net (code "59") (name "/RX3") (class "Default")
      (node (ref "J4") (pin "4") (pinfunction "4_4") (pintype "passive"))
      (node (ref "U3") (pin "7") (pinfunction "7/RX3/PWM_7") (pintype "bidirectional"))
      (node (ref "U9") (pin "RX") (pinfunction "RX_RX") (pintype "bidirectional"))
    )
    (net (code "60") (name "/SCK") (class "Default")
      (node (ref "J5") (pin "1") (pinfunction "1_1") (pintype "passive"))
      (node (ref "U3") (pin "13") (pinfunction "13/SCK0/LED_13") (pintype "bidirectional"))
      (node (ref "U8") (pin "5") (pinfunction "SCK_5") (pintype "bidirectional"))
    )
    (net (code "61") (name "/SCL") (class "Default")
      (node (ref "PCA9685") (pin "26") (pinfunction "SCL_26") (pintype "bidirectional"))
      (node (ref "R31") (pin "P$1") (pinfunction "1_P$1") (pintype "passive"))
      (node (ref "SCL") (pin "1") (pinfunction "1_1") (pintype "passive"))
      (node (ref "U3") (pin "19/A5") (pinfunction "19/A5/SCL0_19/A5") (pintype "bidirectional"))
      (node (ref "U5") (pin "SCL") (pinfunction "SCL_SCL") (pintype "bidirectional"))
      (node (ref "U6") (pin "SCL") (pinfunction "SCL_SCL") (pintype "bidirectional"))
    )
    (net (code "62") (name "/SDA") (class "Default")
      (node (ref "PCA9685") (pin "27") (pinfunction "SDA_27") (pintype "bidirectional"))
      (node (ref "R30") (pin "P$1") (pinfunction "1_P$1") (pintype "passive"))
      (node (ref "SDA") (pin "1") (pinfunction "1_1") (pintype "passive"))
      (node (ref "U3") (pin "18/A4") (pinfunction "18/A4/SDA0_18/A4") (pintype "bidirectional"))
      (node (ref "U5") (pin "SDA") (pinfunction "SDA_SDA") (pintype "bidirectional"))
      (node (ref "U6") (pin "SDA") (pinfunction "SDA_SDA") (pintype "bidirectional"))
    )
    (net (code "63") (name "/TX1") (class "Default")
      (node (ref "J7") (pin "2") (pinfunction "2_2") (pintype "passive"))
      (node (ref "U3") (pin "1") (pinfunction "1/TX1/MISO1_1") (pintype "bidirectional"))
    )
    (net (code "64") (name "/TX2") (class "Default")
      (node (ref "J3") (pin "2") (pinfunction "2_2") (pintype "passive"))
      (node (ref "U3") (pin "10") (pinfunction "10/TX2/PWM_10") (pintype "bidirectional"))
    )
    (net (code "65") (name "/TX3") (class "Default")
      (node (ref "J4") (pin "3") (pinfunction "3_3") (pintype "passive"))
      (node (ref "U3") (pin "8") (pinfunction "8/TX3/PWM_8") (pintype "bidirectional"))
      (node (ref "U9") (pin "TX") (pinfunction "TX_TX") (pintype "bidirectional"))
    )
    (net (code "66") (name "/TX_2") (class "Default")
      (node (ref "J5") (pin "4") (pinfunction "4_4") (pintype "passive"))
      (node (ref "U8") (pin "8") (pinfunction "CS_8") (pintype "bidirectional"))
    )
    (net (code "67") (name "/VUSB") (class "Default")
      (node (ref "J11") (pin "3") (pinfunction "3_3") (pintype "passive"))
      (node (ref "U3") (pin "VUSB") (pinfunction "VUSB_VUSB") (pintype "power_in"))
    )
    (net (code "68") (name "/WHITE_LED") (class "Default")
      (node (ref "D4") (pin "A") (pinfunction "A_A") (pintype "passive"))
      (node (ref "U3") (pin "23/A9") (pinfunction "23/A9/PWM_23/A9") (pintype "bidirectional"))
    )
    (net (code "69") (name "/YELLOW_LED") (class "Default")
      (node (ref "D3") (pin "A") (pinfunction "A_A") (pintype "passive"))
      (node (ref "U3") (pin "22/A8") (pinfunction "22/A8/PWM_22/A8") (pintype "bidirectional"))
    )
    (net (code "70") (name "Net-(C1-+)") (class "Default")
      (node (ref "BAT") (pin "1") (pinfunction "1_1") (pintype "passive"))
      (node (ref "BAT_VIN") (pin "1") (pinfunction "1_1") (pintype "passive"))
      (node (ref "C1") (pin "1") (pinfunction "+_1") (pintype "passive"))
      (node (ref "C6") (pin "1") (pinfunction "+_1") (pintype "passive"))
      (node (ref "IC1") (pin "1") (pinfunction "~{SHDN}_1") (pintype "input"))
      (node (ref "IC1") (pin "2") (pinfunction "IN_2") (pintype "input"))
      (node (ref "IC2") (pin "1") (pinfunction "~{SHDN}_1") (pintype "input"))
      (node (ref "IC2") (pin "2") (pinfunction "IN_2") (pintype "input"))
      (node (ref "J12") (pin "2") (pinfunction "2_2") (pintype "passive"))
    )
    (net (code "71") (name "Net-(D1-C)") (class "Default")
      (node (ref "D1") (pin "K") (pinfunction "C_K") (pintype "passive"))
      (node (ref "R1") (pin "P$2") (pinfunction "2_P$2") (pintype "passive"))
    )
    (net (code "72") (name "Net-(D2-C)") (class "Default")
      (node (ref "D2") (pin "K") (pinfunction "C_K") (pintype "passive"))
      (node (ref "R2") (pin "P$2") (pinfunction "2_P$2") (pintype "passive"))
    )
    (net (code "73") (name "Net-(D3-C)") (class "Default")
      (node (ref "D3") (pin "K") (pinfunction "C_K") (pintype "passive"))
      (node (ref "R3") (pin "P$2") (pinfunction "2_P$2") (pintype "passive"))
    )
    (net (code "74") (name "Net-(D4-C)") (class "Default")
      (node (ref "D4") (pin "K") (pinfunction "C_K") (pintype "passive"))
      (node (ref "R5") (pin "P$2") (pinfunction "2_P$2") (pintype "passive"))
    )
    (net (code "75") (name "Net-(D5-C)") (class "Default")
      (node (ref "D5") (pin "K") (pinfunction "C_K") (pintype "passive"))
      (node (ref "R4") (pin "P$2") (pinfunction "2_P$2") (pintype "passive"))
    )
    (net (code "76") (name "Net-(G0-P)") (class "Default")
      (node (ref "G0") (pin "1") (pinfunction "P_1") (pintype "passive"))
      (node (ref "U8") (pin "4") (pinfunction "G0_4") (pintype "bidirectional"))
    )
    (net (code "77") (name "Net-(G1-P)") (class "Default")
      (node (ref "G1") (pin "1") (pinfunction "P_1") (pintype "passive"))
      (node (ref "U8") (pin "10") (pinfunction "G1_10") (pintype "bidirectional"))
    )
    (net (code "78") (name "Net-(G2-P)") (class "Default")
      (node (ref "G2") (pin "1") (pinfunction "P_1") (pintype "passive"))
      (node (ref "U8") (pin "11") (pinfunction "G2_11") (pintype "bidirectional"))
    )
    (net (code "79") (name "Net-(G3-P)") (class "Default")
      (node (ref "G3") (pin "1") (pinfunction "P_1") (pintype "passive"))
      (node (ref "U8") (pin "12") (pinfunction "G3_12") (pintype "bidirectional"))
    )
    (net (code "80") (name "Net-(G4-P)") (class "Default")
      (node (ref "G4") (pin "1") (pinfunction "P_1") (pintype "passive"))
      (node (ref "U8") (pin "13") (pinfunction "G4_13") (pintype "bidirectional"))
    )
    (net (code "81") (name "Net-(G5-P)") (class "Default")
      (node (ref "G5") (pin "1") (pinfunction "P_1") (pintype "passive"))
      (node (ref "U8") (pin "14") (pinfunction "G5_14") (pintype "bidirectional"))
    )
    (net (code "82") (name "Net-(IC1-SENSE)") (class "Default")
      (node (ref "IC1") (pin "5") (pinfunction "SENSE_5") (pintype "input"))
      (node (ref "R28") (pin "P$2") (pinfunction "2_P$2") (pintype "passive"))
      (node (ref "R29") (pin "P$1") (pinfunction "1_P$1") (pintype "passive"))
    )
    (net (code "83") (name "Net-(IC2-SENSE)") (class "Default")
      (node (ref "IC2") (pin "5") (pinfunction "SENSE_5") (pintype "input"))
      (node (ref "R26") (pin "P$2") (pinfunction "2_P$2") (pintype "passive"))
      (node (ref "R27") (pin "P$1") (pinfunction "1_P$1") (pintype "passive"))
    )
    (net (code "84") (name "Net-(R10-2)") (class "Default")
      (node (ref "JP1") (pin "1") (pinfunction "1_1") (pintype "passive"))
      (node (ref "R10") (pin "P$2") (pinfunction "2_P$2") (pintype "passive"))
    )
    (net (code "85") (name "Net-(R11-2)") (class "Default")
      (node (ref "JP2") (pin "1") (pinfunction "1_1") (pintype "passive"))
      (node (ref "R11") (pin "P$2") (pinfunction "2_P$2") (pintype "passive"))
    )
    (net (code "86") (name "Net-(R12-2)") (class "Default")
      (node (ref "JP3") (pin "1") (pinfunction "1_1") (pintype "passive"))
      (node (ref "R12") (pin "P$2") (pinfunction "2_P$2") (pintype "passive"))
    )
    (net (code "87") (name "Net-(R13-2)") (class "Default")
      (node (ref "JP4") (pin "1") (pinfunction "1_1") (pintype "passive"))
      (node (ref "R13") (pin "P$2") (pinfunction "2_P$2") (pintype "passive"))
    )
    (net (code "88") (name "Net-(R14-2)") (class "Default")
      (node (ref "JP5") (pin "1") (pinfunction "1_1") (pintype "passive"))
      (node (ref "R14") (pin "P$2") (pinfunction "2_P$2") (pintype "passive"))
    )
    (net (code "89") (name "Net-(R15-2)") (class "Default")
      (node (ref "JP6") (pin "1") (pinfunction "1_1") (pintype "passive"))
      (node (ref "R15") (pin "P$2") (pinfunction "2_P$2") (pintype "passive"))
    )
    (net (code "90") (name "Net-(R16-2)") (class "Default")
      (node (ref "JP7") (pin "1") (pinfunction "1_1") (pintype "passive"))
      (node (ref "R16") (pin "P$2") (pinfunction "2_P$2") (pintype "passive"))
    )
    (net (code "91") (name "Net-(R17-2)") (class "Default")
      (node (ref "JP8") (pin "1") (pinfunction "1_1") (pintype "passive"))
      (node (ref "R17") (pin "P$2") (pinfunction "2_P$2") (pintype "passive"))
    )
    (net (code "92") (name "Net-(R18-2)") (class "Default")
      (node (ref "JP9") (pin "1") (pinfunction "1_1") (pintype "passive"))
      (node (ref "R18") (pin "P$2") (pinfunction "2_P$2") (pintype "passive"))
    )
    (net (code "93") (name "Net-(R19-2)") (class "Default")
      (node (ref "JP10") (pin "1") (pinfunction "1_1") (pintype "passive"))
      (node (ref "R19") (pin "P$2") (pinfunction "2_P$2") (pintype "passive"))
    )
    (net (code "94") (name "Net-(R20-2)") (class "Default")
      (node (ref "JP11") (pin "1") (pinfunction "1_1") (pintype "passive"))
      (node (ref "R20") (pin "P$2") (pinfunction "2_P$2") (pintype "passive"))
    )
    (net (code "95") (name "Net-(R21-2)") (class "Default")
      (node (ref "JP12") (pin "1") (pinfunction "1_1") (pintype "passive"))
      (node (ref "R21") (pin "P$2") (pinfunction "2_P$2") (pintype "passive"))
    )
    (net (code "96") (name "Net-(R22-2)") (class "Default")
      (node (ref "JP13") (pin "1") (pinfunction "1_1") (pintype "passive"))
      (node (ref "R22") (pin "P$2") (pinfunction "2_P$2") (pintype "passive"))
    )
    (net (code "97") (name "Net-(R23-2)") (class "Default")
      (node (ref "JP14") (pin "1") (pinfunction "1_1") (pintype "passive"))
      (node (ref "R23") (pin "P$2") (pinfunction "2_P$2") (pintype "passive"))
    )
    (net (code "98") (name "Net-(R24-2)") (class "Default")
      (node (ref "JP15") (pin "1") (pinfunction "1_1") (pintype "passive"))
      (node (ref "R24") (pin "P$2") (pinfunction "2_P$2") (pintype "passive"))
    )
    (net (code "99") (name "Net-(R25-2)") (class "Default")
      (node (ref "JP16") (pin "1") (pinfunction "1_1") (pintype "passive"))
      (node (ref "R25") (pin "P$2") (pinfunction "2_P$2") (pintype "passive"))
    )
    (net (code "100") (name "unconnected-(U5-PadAUXCL)") (class "Default")
      (node (ref "U5") (pin "AUXCL") (pinfunction "AUXCL_AUXCL") (pintype "bidirectional"))
    )
    (net (code "101") (name "unconnected-(U5-PadAUXDA)") (class "Default")
      (node (ref "U5") (pin "AUXDA") (pinfunction "AUXDA_AUXDA") (pintype "bidirectional"))
    )
    (net (code "102") (name "unconnected-(U5-PadCS)") (class "Default")
      (node (ref "U5") (pin "CS") (pinfunction "CS_CS") (pintype "bidirectional"))
    )
    (net (code "103") (name "unconnected-(U5-PadVDDIO)") (class "Default")
      (node (ref "U5") (pin "VDDIO") (pinfunction "VDDIO_VDDIO") (pintype "bidirectional"))
    )
    (net (code "104") (name "unconnected-(U6-Pad3VO)") (class "Default")
      (node (ref "U6") (pin "3VO") (pinfunction "3VO_3VO") (pintype "bidirectional"))
    )
    (net (code "105") (name "unconnected-(U9-Pad3.3V)") (class "Default")
      (node (ref "U9") (pin "3.3V") (pinfunction "3.3V_3.3V") (pintype "bidirectional"))
    )
    (net (code "106") (name "unconnected-(U9-PadVBAT)") (class "Default")
      (node (ref "U9") (pin "VBAT") (pinfunction "VBAT_VBAT") (pintype "bidirectional"))
    )
  )
)
